# Relais2-N_Channel_MOSFET-V002.net
KiCad netlist of a schematic drawn in EAGLE
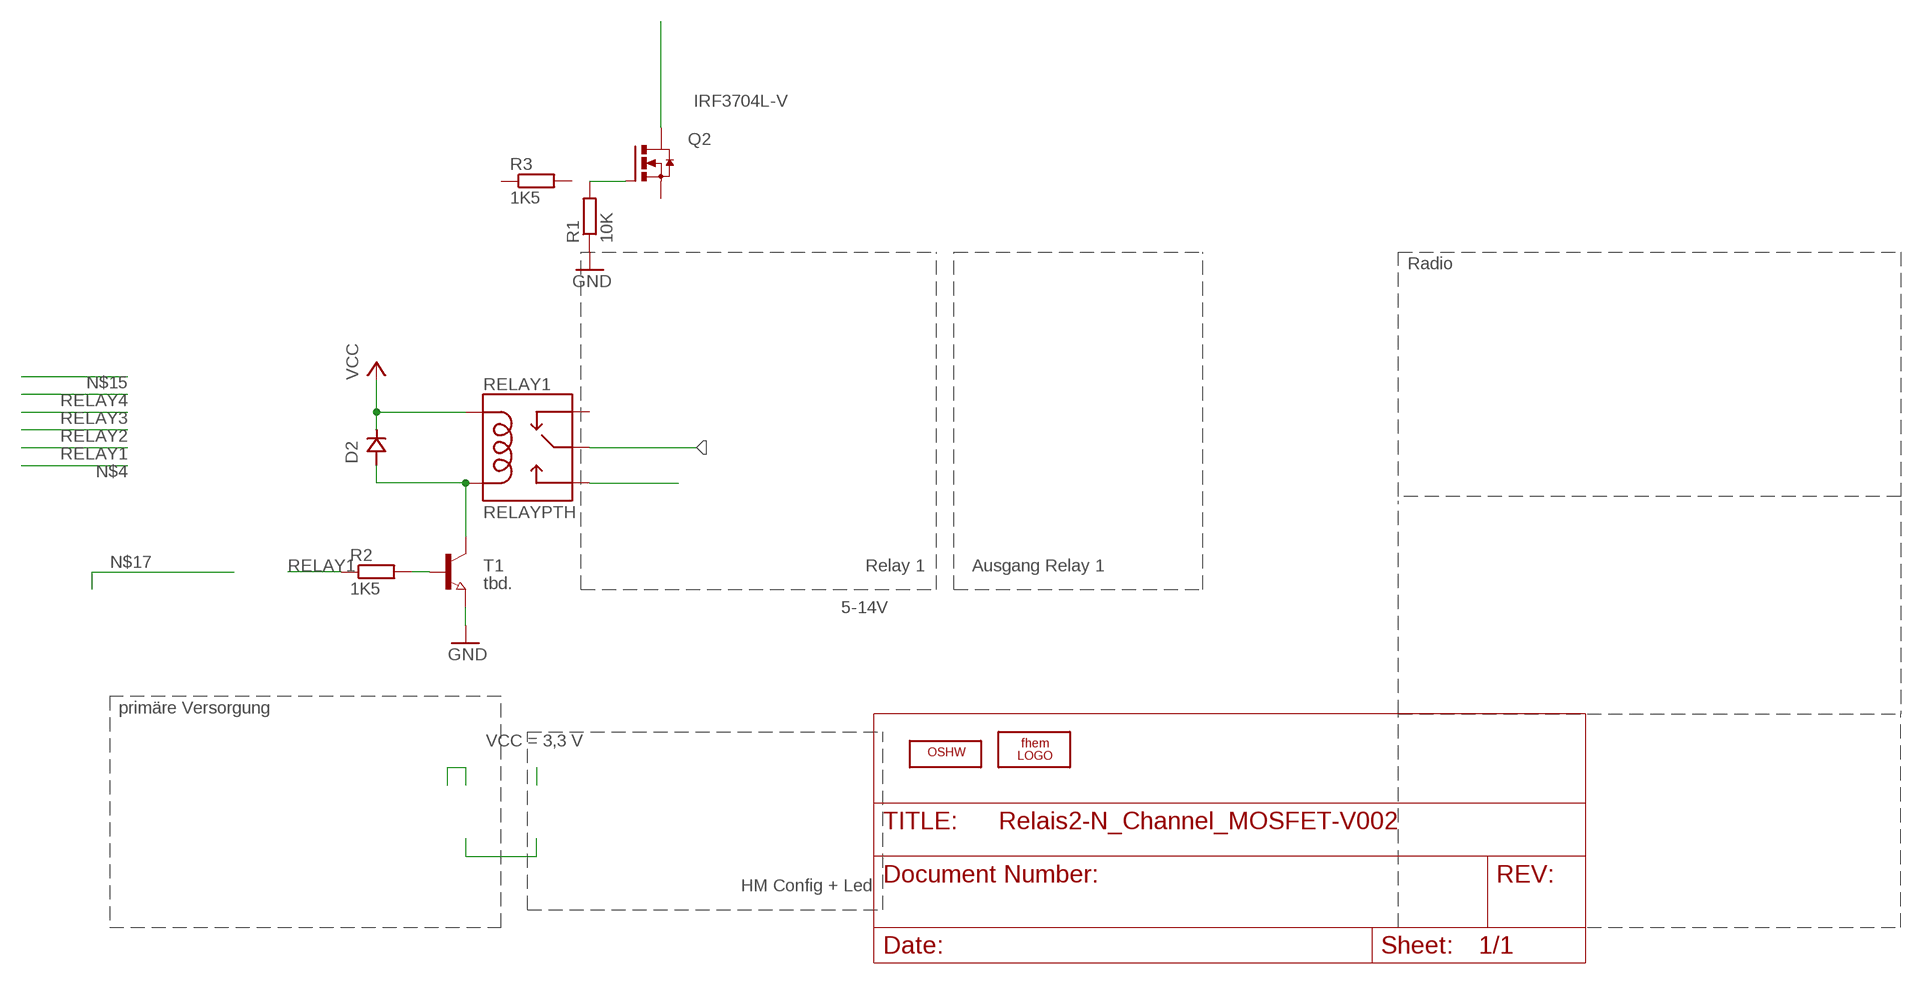
[diagram p0: schematic, sheet 1]

(export (version "E")
  (design (tool "Eeschema 10.0.6"))
  (components
    (comp (ref "D2")
      (value "SS14")
      (footprint "eagle-import:DO214")
      (libsource (lib "eagle-import") (part "SS14"))
    )
    (comp (ref "LOGO2")
      (value "LOGO_OSHWX0070")
      (footprint "eagle-import:OSHW_6X70")
      (libsource (lib "eagle-import") (part "LOGO_OSHWX0070"))
    )
    (comp (ref "Q2")
      (value "IRF3704L-V")
      (footprint "eagle-import:TO262-V")
      (libsource (lib "eagle-import") (part "IRF3704L-V"))
    )
    (comp (ref "R1")
      (value "10K")
      (footprint "eagle-import:R0805_SMALL_GAP")
      (libsource (lib "eagle-import") (part "R0805_SMALL_GAP"))
    )
    (comp (ref "R2")
      (value "1K5")
      (footprint "eagle-import:R0805_SMALL_GAP")
      (libsource (lib "eagle-import") (part "R0805_SMALL_GAP"))
    )
    (comp (ref "R3")
      (value "1K5")
      (footprint "eagle-import:R0805_SMALL_GAP")
      (libsource (lib "eagle-import") (part "R0805_SMALL_GAP"))
    )
    (comp (ref "RELAY1")
      (value "RELAYPTH")
      (footprint "eagle-import:SRD-05VDC-SL-C")
      (libsource (lib "eagle-import") (part "RELAYPTH"))
    )
    (comp (ref "T1")
      (value "tbd.")
      (footprint "eagle-import:SOT89")
      (libsource (lib "eagle-import") (part "NPN-TRANSISTOR_SOT89"))
    )
    (comp (ref "U$2")
      (value "LOGO_FHEMSTOP")
      (footprint "eagle-import:LOGO_FHEM_3X3_STOP")
      (libsource (lib "eagle-import") (part "LOGO_FHEMSTOP"))
    )
  )
  (nets
    (net (code "4") (name "/RELAY1") (class "Default")
      (node (ref "R2") (pin "1") (pinfunction "1_1") (pintype "passive"))
    )
    (net (code "8") (name "GND") (class "Default")
      (node (ref "R1") (pin "1") (pinfunction "1_1") (pintype "passive"))
      (node (ref "T1") (pin "3") (pinfunction "E_3") (pintype "passive"))
    )
    (net (code "9") (name "Net-(Q2-G)") (class "Default")
      (node (ref "Q2") (pin "1") (pinfunction "G_1") (pintype "passive"))
      (node (ref "R1") (pin "2") (pinfunction "2_2") (pintype "passive"))
    )
    (net (code "10") (name "Net-(T1-B)") (class "Default")
      (node (ref "R2") (pin "2") (pinfunction "2_2") (pintype "passive"))
      (node (ref "T1") (pin "1") (pinfunction "B_1") (pintype "passive"))
    )
    (net (code "11") (name "Net-(T1-C)") (class "Default")
      (node (ref "D2") (pin "ANODE") (pinfunction "ANODE_ANODE") (pintype "bidirectional"))
      (node (ref "RELAY1") (pin "COIL0") (pinfunction "COIL0_COIL0") (pintype "bidirectional"))
      (node (ref "T1") (pin "2") (pinfunction "C_2") (pintype "passive"))
    )
    (net (code "12") (name "SW-INPUT") (class "Default")
      (node (ref "RELAY1") (pin "SWCOMMON") (pinfunction "SWCOMMON_SWCOMMON") (pintype "bidirectional"))
    )
    (net (code "13") (name "VCC") (class "Default")
      (node (ref "D2") (pin "CATHODE") (pinfunction "CATHODE_CATHODE") (pintype "bidirectional"))
      (node (ref "RELAY1") (pin "COIL1") (pinfunction "COIL1_COIL1") (pintype "bidirectional"))
    )
    (net (code "14") (name "unconnected-(Q2-D-Pad2)") (class "Default")
      (node (ref "Q2") (pin "2") (pinfunction "D_2") (pintype "passive"))
    )
    (net (code "15") (name "unconnected-(Q2-S-Pad3)") (class "Default")
      (node (ref "Q2") (pin "3") (pinfunction "S_3") (pintype "passive"))
    )
    (net (code "16") (name "unconnected-(R3-Pad1)") (class "Default")
      (node (ref "R3") (pin "1") (pinfunction "1_1") (pintype "passive"))
    )
    (net (code "17") (name "unconnected-(R3-Pad2)") (class "Default")
      (node (ref "R3") (pin "2") (pinfunction "2_2") (pintype "passive"))
    )
    (net (code "18") (name "unconnected-(RELAY1-PadSWOPEN)") (class "Default")
      (node (ref "RELAY1") (pin "SWOPEN") (pinfunction "SWOPEN_SWOPEN") (pintype "bidirectional"))
    )
    (net (code "19") (name "unconnected-(RELAY1-SWCLOSE-PadSWCLOSED)") (class "Default")
      (node (ref "RELAY1") (pin "SWCLOSED") (pinfunction "SWCLOSE_SWCLOSED") (pintype "bidirectional"))
    )
  )
)
